# S7CAS-PLEIADES-CARTE-MERE_P06_USB_PROGRA.net
KiCad netlist of a schematic drawn in Altium Designer
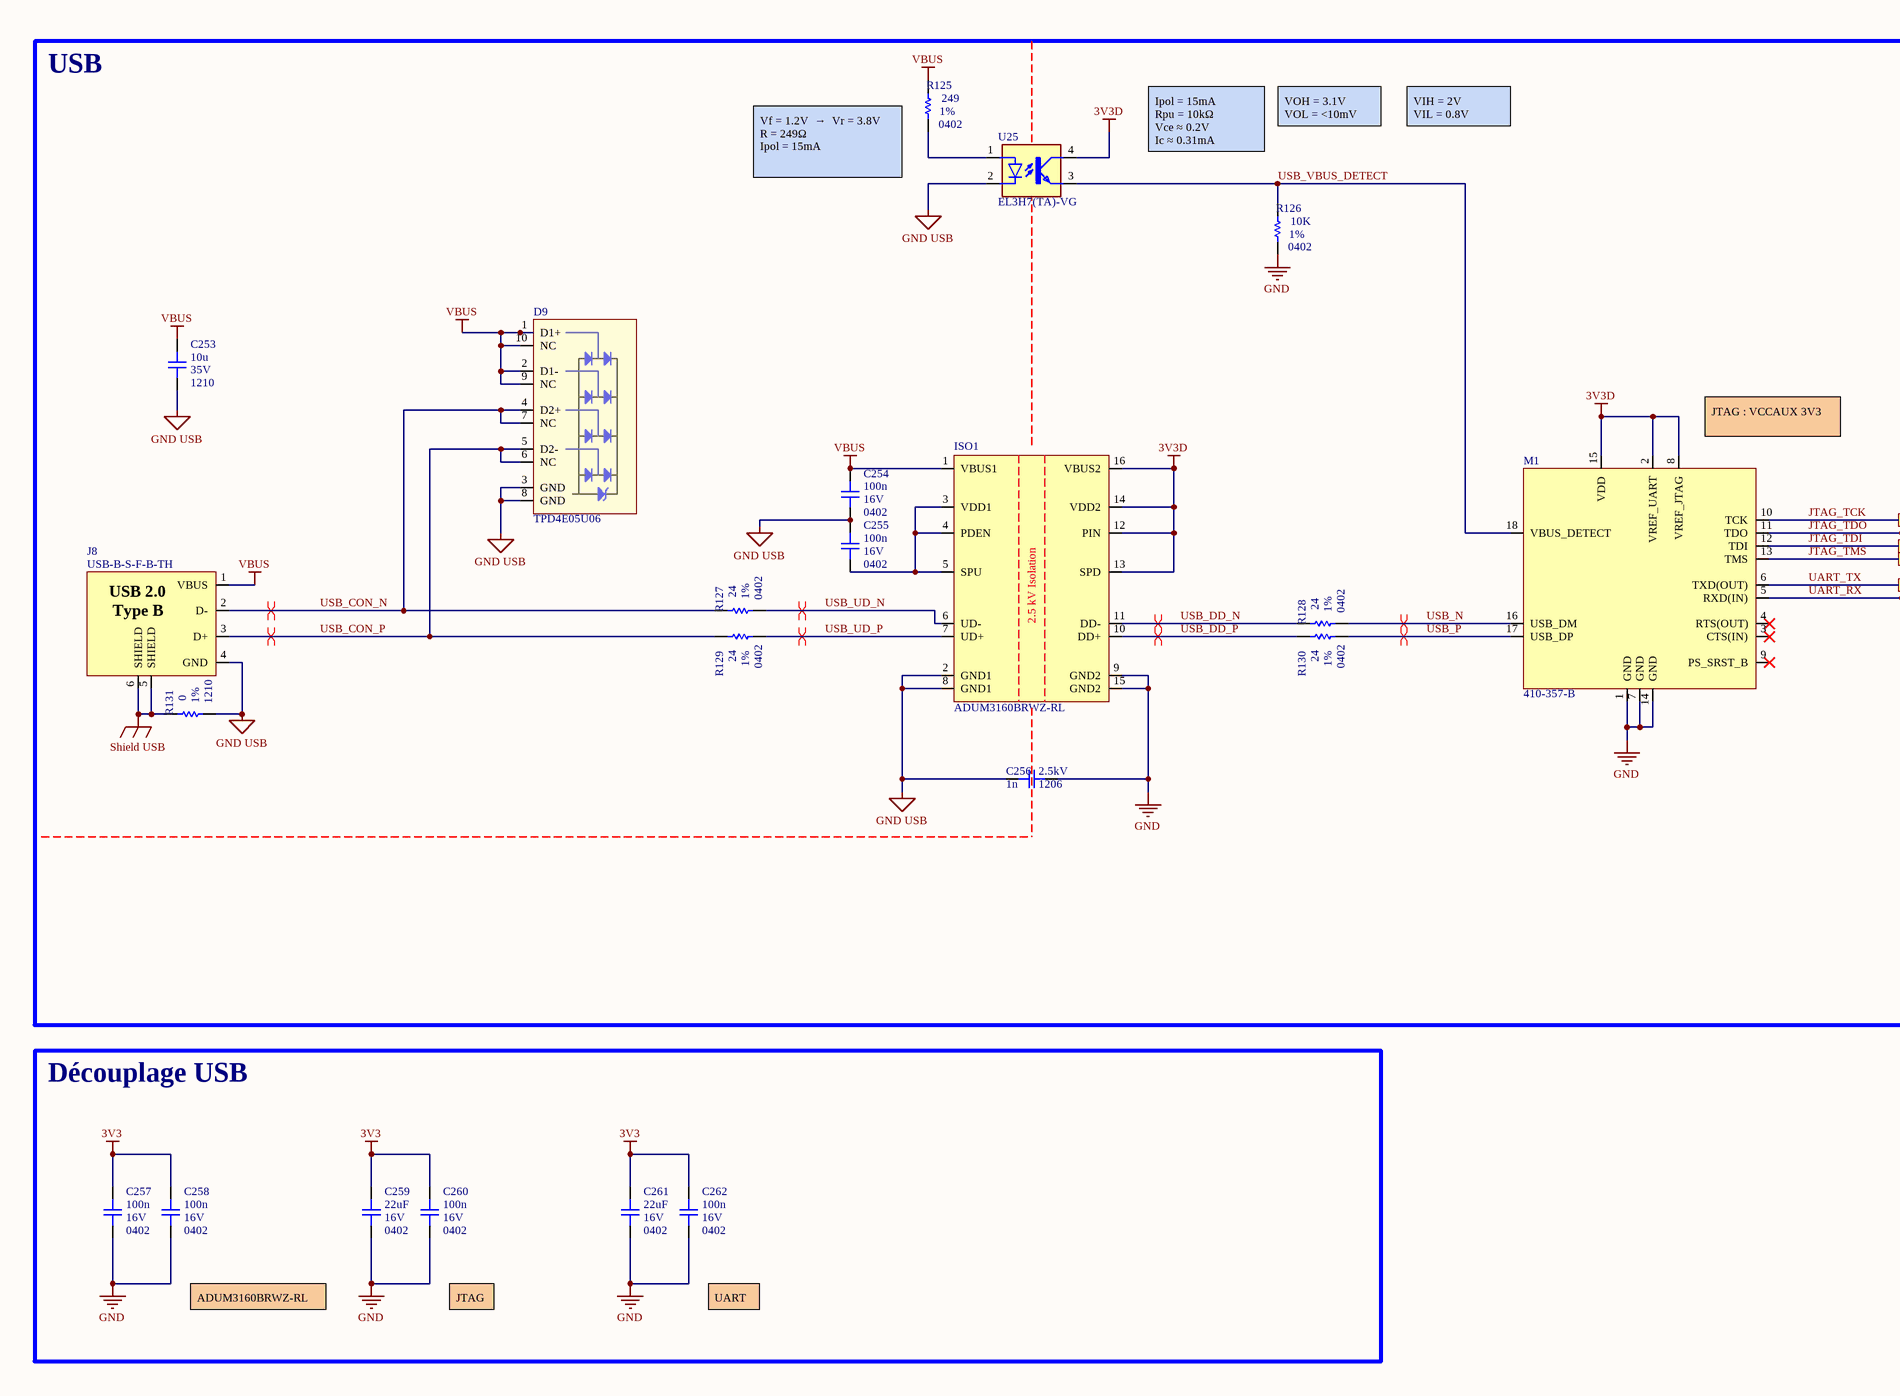
[diagram p0: S7CAS-PLEIADES-CARTE-MERE_P06_USB_PROGRAMER.SCHDOC, left]
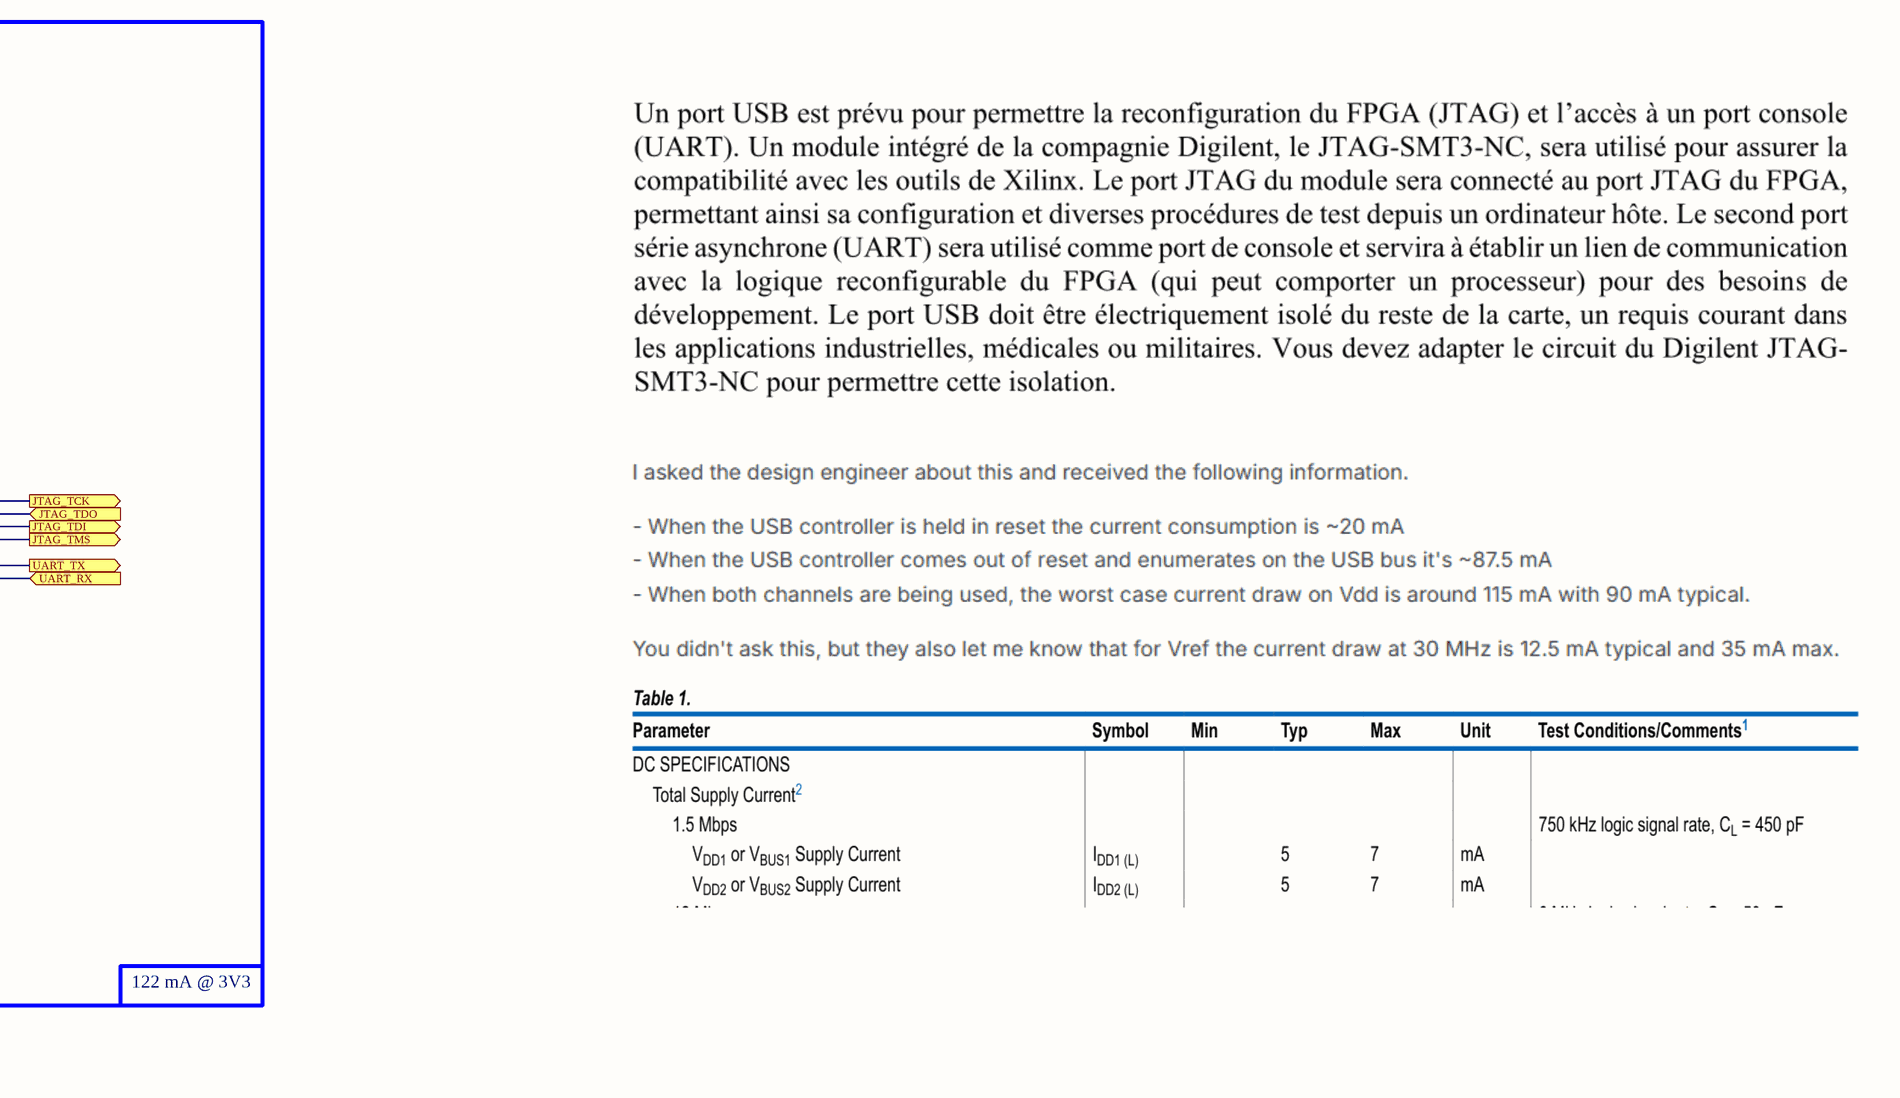
[diagram p1: S7CAS-PLEIADES-CARTE-MERE_P06_USB_PROGRAMER.SCHDOC, right]

(export (version "E")
  (design (tool "Eeschema 10.0.6"))
  (components
    (comp (ref "C253")
      (value "10u")
      (footprint "CAP_1210")
      (description "CAP - 1210")
      (fields
        (field (name "VOLTAGE") "35V")
        (field (name "PACKAGE") "1210")
        (field (name "CREATEDBY") "Jonathan Bouchard")
      )
      (libsource (lib "s7cas_lib2023") (part "CAP - 1210"))
    )
    (comp (ref "C254")
      (value "100n")
      (footprint "CAP_0402")
      (description "CAP - 0402")
      (fields
        (field (name "VOLTAGE") "16V")
        (field (name "PACKAGE") "0402")
        (field (name "CREATEDBY") "Jonathan Bouchard")
      )
      (libsource (lib "s7cas_lib2023") (part "CAP - 0402"))
    )
    (comp (ref "C255")
      (value "100n")
      (footprint "CAP_0402")
      (description "CAP - 0402")
      (fields
        (field (name "VOLTAGE") "16V")
        (field (name "PACKAGE") "0402")
        (field (name "CREATEDBY") "Jonathan Bouchard")
      )
      (libsource (lib "s7cas_lib2023") (part "CAP - 0402"))
    )
    (comp (ref "C256")
      (value "1n")
      (footprint "CAP_0402")
      (description "CAP - 0402")
      (fields
        (field (name "VOLTAGE") "2.5kV")
        (field (name "PACKAGE") "1206")
        (field (name "CREATEDBY") "Jonathan Bouchard")
      )
      (libsource (lib "s7cas_lib2023") (part "CAP - 0402"))
    )
    (comp (ref "C257")
      (value "100n")
      (footprint "CAP_0402")
      (description "CAP - 0402")
      (fields
        (field (name "VOLTAGE") "16V")
        (field (name "PACKAGE") "0402")
        (field (name "CREATEDBY") "Jonathan Bouchard")
      )
      (libsource (lib "s7cas_lib2023") (part "CAP - 0402"))
    )
    (comp (ref "C258")
      (value "100n")
      (footprint "CAP_0402")
      (description "CAP - 0402")
      (fields
        (field (name "VOLTAGE") "16V")
        (field (name "PACKAGE") "0402")
        (field (name "CREATEDBY") "Jonathan Bouchard")
      )
      (libsource (lib "s7cas_lib2023") (part "CAP - 0402"))
    )
    (comp (ref "C259")
      (value "22uF")
      (footprint "CAP_0402")
      (description "CAP - 0402")
      (fields
        (field (name "VOLTAGE") "16V")
        (field (name "PACKAGE") "0402")
        (field (name "CREATEDBY") "Jonathan Bouchard")
      )
      (libsource (lib "s7cas_lib2023") (part "CAP - 0402"))
    )
    (comp (ref "C260")
      (value "100n")
      (footprint "CAP_0402")
      (description "CAP - 0402")
      (fields
        (field (name "VOLTAGE") "16V")
        (field (name "PACKAGE") "0402")
        (field (name "CREATEDBY") "Jonathan Bouchard")
      )
      (libsource (lib "s7cas_lib2023") (part "CAP - 0402"))
    )
    (comp (ref "C261")
      (value "22uF")
      (footprint "CAP_0402")
      (description "CAP - 0402")
      (fields
        (field (name "VOLTAGE") "16V")
        (field (name "PACKAGE") "0402")
        (field (name "CREATEDBY") "Jonathan Bouchard")
      )
      (libsource (lib "s7cas_lib2023") (part "CAP - 0402"))
    )
    (comp (ref "C262")
      (value "100n")
      (footprint "CAP_0402")
      (description "CAP - 0402")
      (fields
        (field (name "VOLTAGE") "16V")
        (field (name "PACKAGE") "0402")
        (field (name "CREATEDBY") "Jonathan Bouchard")
      )
      (libsource (lib "s7cas_lib2023") (part "CAP - 0402"))
    )
    (comp (ref "D9")
      (value "TPD4E05U06")
      (footprint "TVS_DATA_TPD4E05U06")
      (description "TVS - TVS DIODE 5.5VWM 14VC - 10SON")
      (fields
        (field (name "CREATEDBY/DATE") "Olivier Bernard / 12/3/2018")
        (field (name "VERIFIEDBY") "Caroline Paulin / 4 juillet 2018")
      )
      (libsource (lib "s7cas_lib2023") (part "TVS_DATA_TPD4E05U06"))
    )
    (comp (ref "ISO1")
      (value "ADUM3160BRWZ-RL")
      (footprint "ISO_ADUM3160BRWZ-RL")
      (description "ISO - DGTL ISO 2.5KV 2CH USB - 16SOIC")
      (fields
        (field (name "CREATEDBY/DATE") "Tommy Rossignol 2018-11-16")
        (field (name "VERIFIEDBY") "Caroline Paulin - 13 février 2019")
      )
      (libsource (lib "s7cas_lib2023") (part "ISO_ADUM3160BRWZ-RL"))
    )
    (comp (ref "J8")
      (value "USB-B-S-F-B-TH")
      (footprint "CON_USB_USB-B-S-F-B-TH")
      (description "CON - USB B RECPT TH R/A - 4-TH")
      (fields
        (field (name "CREATEDBY/DATE") "Jonathan Bouchard 2020-03-24")
        (field (name "VERIFIEDBY") "C.Paulin - 22/04/2020")
      )
      (libsource (lib "s7cas_lib2023") (part "CON_USB_USB-B-S-F-B-TH"))
    )
    (comp (ref "M1")
      (value "410-357-B")
      (footprint "MOD_JTAG_410-357-B")
      (description "MOD - JTAG-SMT3-NC Programming Module For Xilinx FPGA - 18-SMT")
      (fields
        (field (name "CREATEDBY/DATE") "Tommy Rossignol 2018-11-23")
        (field (name "VERIFIEDBY") "Nicolas V. (2019-01-28)")
      )
      (libsource (lib "s7cas_lib2023") (part "MOD_JTAG_410-357-B"))
    )
    (comp (ref "R125")
      (value "249")
      (footprint "RES_0402")
      (description "RES - 0402")
      (fields
        (field (name "VOLTAGE") "50V")
        (field (name "POWER") "1/16W")
        (field (name "PACKAGE") "0402")
        (field (name "PRECISION") "1%")
        (field (name "CREATEDBY") "Jonathan Bouchard")
      )
      (libsource (lib "s7cas_lib2023") (part "RES - 0402"))
    )
    (comp (ref "R126")
      (value "10K")
      (footprint "RES_0402")
      (description "RES - 0402")
      (fields
        (field (name "VOLTAGE") "50V")
        (field (name "POWER") "1/16W")
        (field (name "PACKAGE") "0402")
        (field (name "PRECISION") "1%")
        (field (name "CREATEDBY") "Jonathan Bouchard")
      )
      (libsource (lib "s7cas_lib2023") (part "RES - 0402"))
    )
    (comp (ref "R127")
      (value "24")
      (footprint "RES_0402")
      (description "RES - 0402")
      (fields
        (field (name "VOLTAGE") "50V")
        (field (name "POWER") "1/16W")
        (field (name "PACKAGE") "0402")
        (field (name "PRECISION") "1%")
        (field (name "CREATEDBY") "Jonathan Bouchard")
      )
      (libsource (lib "s7cas_lib2023") (part "RES - 0402"))
    )
    (comp (ref "R128")
      (value "24")
      (footprint "RES_0402")
      (description "RES - 0402")
      (fields
        (field (name "VOLTAGE") "50V")
        (field (name "POWER") "1/16W")
        (field (name "PACKAGE") "0402")
        (field (name "PRECISION") "1%")
        (field (name "CREATEDBY") "Jonathan Bouchard")
      )
      (libsource (lib "s7cas_lib2023") (part "RES - 0402"))
    )
    (comp (ref "R129")
      (value "24")
      (footprint "RES_0402")
      (description "RES - 0402")
      (fields
        (field (name "VOLTAGE") "50V")
        (field (name "POWER") "1/16W")
        (field (name "PACKAGE") "0402")
        (field (name "PRECISION") "1%")
        (field (name "CREATEDBY") "Jonathan Bouchard")
      )
      (libsource (lib "s7cas_lib2023") (part "RES - 0402"))
    )
    (comp (ref "R130")
      (value "24")
      (footprint "RES_0402")
      (description "RES - 0402")
      (fields
        (field (name "VOLTAGE") "50V")
        (field (name "POWER") "1/16W")
        (field (name "PACKAGE") "0402")
        (field (name "PRECISION") "1%")
        (field (name "CREATEDBY") "Jonathan Bouchard")
      )
      (libsource (lib "s7cas_lib2023") (part "RES - 0402"))
    )
    (comp (ref "R131")
      (value "0")
      (footprint "RES_1210")
      (description "RES - 1210")
      (fields
        (field (name "POWER") "1/16W")
        (field (name "PACKAGE") "1210")
        (field (name "PRECISION") "1%")
        (field (name "CREATEDBY") "Jonathan Bouchard")
      )
      (libsource (lib "s7cas_lib2023") (part "RES - 1210"))
    )
    (comp (ref "U25")
      (value "EL3H7(TA)-VG")
      (footprint "SOIC127P700X200-4N")
      (description "Optoisolator Transistor Output 3750Vrms 1 Channel 4-SSOP")
      (fields (field (name "MF") "Everlight Electronics"))
      (libsource (lib "EL3H7_TA_-VG") (part "EL3H7(TA)-VG"))
    )
  )
  (nets
    (net (code "1") (name "/JTAG_TCK") (class "Default")
      (node (ref "M1") (pin "10") (pinfunction "TCK_10") (pintype "passive"))
    )
    (net (code "2") (name "/JTAG_TDI") (class "Default")
      (node (ref "M1") (pin "12") (pinfunction "TDI_12") (pintype "passive"))
    )
    (net (code "3") (name "/JTAG_TDO") (class "Default")
      (node (ref "M1") (pin "11") (pinfunction "TDO_11") (pintype "passive"))
    )
    (net (code "4") (name "/JTAG_TMS") (class "Default")
      (node (ref "M1") (pin "13") (pinfunction "TMS_13") (pintype "passive"))
    )
    (net (code "5") (name "/UART_RX") (class "Default")
      (node (ref "M1") (pin "5") (pinfunction "RXD(IN)_5") (pintype "passive"))
    )
    (net (code "6") (name "/UART_TX") (class "Default")
      (node (ref "M1") (pin "6") (pinfunction "TXD(OUT)_6") (pintype "passive"))
    )
    (net (code "7") (name "/USB_CON_N") (class "Default")
      (node (ref "D9") (pin "4") (pinfunction "D2+_4") (pintype "passive"))
      (node (ref "D9") (pin "7") (pinfunction "NC_7") (pintype "passive"))
      (node (ref "J8") (pin "2") (pinfunction "D-_2") (pintype "passive"))
      (node (ref "R127") (pin "2") (pinfunction "2_2") (pintype "passive"))
    )
    (net (code "8") (name "/USB_CON_P") (class "Default")
      (node (ref "D9") (pin "5") (pinfunction "D2-_5") (pintype "passive"))
      (node (ref "D9") (pin "6") (pinfunction "NC_6") (pintype "passive"))
      (node (ref "J8") (pin "3") (pinfunction "D+_3") (pintype "passive"))
      (node (ref "R129") (pin "2") (pinfunction "2_2") (pintype "passive"))
    )
    (net (code "9") (name "/USB_DD_N") (class "Default")
      (node (ref "ISO1") (pin "11") (pinfunction "DD-_11") (pintype "passive"))
      (node (ref "R128") (pin "2") (pinfunction "2_2") (pintype "passive"))
    )
    (net (code "10") (name "/USB_DD_P") (class "Default")
      (node (ref "ISO1") (pin "10") (pinfunction "DD+_10") (pintype "passive"))
      (node (ref "R130") (pin "2") (pinfunction "2_2") (pintype "passive"))
    )
    (net (code "11") (name "/USB_N") (class "Default")
      (node (ref "M1") (pin "16") (pinfunction "USB_DM_16") (pintype "passive"))
      (node (ref "R128") (pin "1") (pinfunction "1_1") (pintype "passive"))
    )
    (net (code "12") (name "/USB_P") (class "Default")
      (node (ref "M1") (pin "17") (pinfunction "USB_DP_17") (pintype "passive"))
      (node (ref "R130") (pin "1") (pinfunction "1_1") (pintype "passive"))
    )
    (net (code "13") (name "/USB_UD_N") (class "Default")
      (node (ref "ISO1") (pin "6") (pinfunction "UD-_6") (pintype "passive"))
      (node (ref "R127") (pin "1") (pinfunction "1_1") (pintype "passive"))
    )
    (net (code "14") (name "/USB_UD_P") (class "Default")
      (node (ref "ISO1") (pin "7") (pinfunction "UD+_7") (pintype "passive"))
      (node (ref "R129") (pin "1") (pinfunction "1_1") (pintype "passive"))
    )
    (net (code "15") (name "/USB_VBUS_DETECT") (class "Default")
      (node (ref "M1") (pin "18") (pinfunction "VBUS_DETECT_18") (pintype "passive"))
      (node (ref "R126") (pin "2") (pinfunction "2_2") (pintype "passive"))
      (node (ref "U25") (pin "3") (pinfunction "EMIT_3") (pintype "passive"))
    )
    (net (code "16") (name "3V3") (class "Default")
      (node (ref "C257") (pin "2") (pinfunction "2_2") (pintype "passive"))
      (node (ref "C258") (pin "2") (pinfunction "2_2") (pintype "passive"))
      (node (ref "C259") (pin "2") (pinfunction "2_2") (pintype "passive"))
      (node (ref "C260") (pin "2") (pinfunction "2_2") (pintype "passive"))
      (node (ref "C261") (pin "2") (pinfunction "2_2") (pintype "passive"))
      (node (ref "C262") (pin "2") (pinfunction "2_2") (pintype "passive"))
    )
    (net (code "17") (name "3V3D") (class "Default")
      (node (ref "ISO1") (pin "12") (pinfunction "PIN_12") (pintype "passive"))
      (node (ref "ISO1") (pin "13") (pinfunction "SPD_13") (pintype "passive"))
      (node (ref "ISO1") (pin "14") (pinfunction "VDD2_14") (pintype "passive"))
      (node (ref "ISO1") (pin "16") (pinfunction "VBUS2_16") (pintype "passive"))
      (node (ref "M1") (pin "15") (pinfunction "VDD_15") (pintype "passive"))
      (node (ref "M1") (pin "2") (pinfunction "VREF_UART_2") (pintype "passive"))
      (node (ref "M1") (pin "8") (pinfunction "VREF_JTAG_8") (pintype "passive"))
      (node (ref "U25") (pin "4") (pinfunction "COL_4") (pintype "passive"))
    )
    (net (code "18") (name "GND") (class "Default")
      (node (ref "C256") (pin "1") (pinfunction "1_1") (pintype "passive"))
      (node (ref "C257") (pin "1") (pinfunction "1_1") (pintype "passive"))
      (node (ref "C258") (pin "1") (pinfunction "1_1") (pintype "passive"))
      (node (ref "C259") (pin "1") (pinfunction "1_1") (pintype "passive"))
      (node (ref "C260") (pin "1") (pinfunction "1_1") (pintype "passive"))
      (node (ref "C261") (pin "1") (pinfunction "1_1") (pintype "passive"))
      (node (ref "C262") (pin "1") (pinfunction "1_1") (pintype "passive"))
      (node (ref "ISO1") (pin "15") (pinfunction "GND2_15") (pintype "passive"))
      (node (ref "ISO1") (pin "9") (pinfunction "GND2_9") (pintype "passive"))
      (node (ref "M1") (pin "1") (pinfunction "GND_1") (pintype "passive"))
      (node (ref "M1") (pin "14") (pinfunction "GND_14") (pintype "passive"))
      (node (ref "M1") (pin "7") (pinfunction "GND_7") (pintype "passive"))
      (node (ref "R126") (pin "1") (pinfunction "1_1") (pintype "passive"))
    )
    (net (code "19") (name "GND USB") (class "Default")
      (node (ref "C253") (pin "1") (pinfunction "1_1") (pintype "passive"))
      (node (ref "C254") (pin "1") (pinfunction "1_1") (pintype "passive"))
      (node (ref "C255") (pin "2") (pinfunction "2_2") (pintype "passive"))
      (node (ref "C256") (pin "2") (pinfunction "2_2") (pintype "passive"))
      (node (ref "D9") (pin "3") (pinfunction "GND_3") (pintype "passive"))
      (node (ref "D9") (pin "8") (pinfunction "GND_8") (pintype "passive"))
      (node (ref "ISO1") (pin "2") (pinfunction "GND1_2") (pintype "passive"))
      (node (ref "ISO1") (pin "8") (pinfunction "GND1_8") (pintype "passive"))
      (node (ref "J8") (pin "4") (pinfunction "GND_4") (pintype "passive"))
      (node (ref "R131") (pin "1") (pinfunction "1_1") (pintype "passive"))
      (node (ref "U25") (pin "2") (pinfunction "C_2") (pintype "passive"))
    )
    (net (code "20") (name "Net-(ISO1-PDEN)") (class "Default")
      (node (ref "C255") (pin "1") (pinfunction "1_1") (pintype "passive"))
      (node (ref "ISO1") (pin "3") (pinfunction "VDD1_3") (pintype "passive"))
      (node (ref "ISO1") (pin "4") (pinfunction "PDEN_4") (pintype "passive"))
      (node (ref "ISO1") (pin "5") (pinfunction "SPU_5") (pintype "passive"))
    )
    (net (code "21") (name "Net-(U25-A)") (class "Default")
      (node (ref "R125") (pin "1") (pinfunction "1_1") (pintype "passive"))
      (node (ref "U25") (pin "1") (pinfunction "A_1") (pintype "passive"))
    )
    (net (code "22") (name "Shield USB") (class "Default")
      (node (ref "J8") (pin "5") (pinfunction "SHIELD_5") (pintype "passive"))
      (node (ref "J8") (pin "6") (pinfunction "SHIELD_6") (pintype "passive"))
      (node (ref "R131") (pin "2") (pinfunction "2_2") (pintype "passive"))
    )
    (net (code "23") (name "VBUS") (class "Default")
      (node (ref "C253") (pin "2") (pinfunction "2_2") (pintype "passive"))
      (node (ref "C254") (pin "2") (pinfunction "2_2") (pintype "passive"))
      (node (ref "D9") (pin "1") (pinfunction "D1+_1") (pintype "passive"))
      (node (ref "D9") (pin "10") (pinfunction "NC_10") (pintype "passive"))
      (node (ref "D9") (pin "2") (pinfunction "D1-_2") (pintype "passive"))
      (node (ref "D9") (pin "9") (pinfunction "NC_9") (pintype "passive"))
      (node (ref "ISO1") (pin "1") (pinfunction "VBUS1_1") (pintype "passive"))
      (node (ref "J8") (pin "1") (pinfunction "VBUS_1") (pintype "passive"))
      (node (ref "R125") (pin "2") (pinfunction "2_2") (pintype "passive"))
    )
    (net (code "24") (name "unconnected-(M1-CTS(IN)-Pad3)") (class "Default")
      (node (ref "M1") (pin "3") (pinfunction "CTS(IN)_3") (pintype "passive+no_connect"))
    )
    (net (code "25") (name "unconnected-(M1-PS_SRST_B-Pad9)") (class "Default")
      (node (ref "M1") (pin "9") (pinfunction "PS_SRST_B_9") (pintype "passive+no_connect"))
    )
    (net (code "26") (name "unconnected-(M1-RTS(OUT)-Pad4)") (class "Default")
      (node (ref "M1") (pin "4") (pinfunction "RTS(OUT)_4") (pintype "passive+no_connect"))
    )
  )
)
